# draftAccelTemp.net
KiCad netlist of a schematic drawn in EAGLE
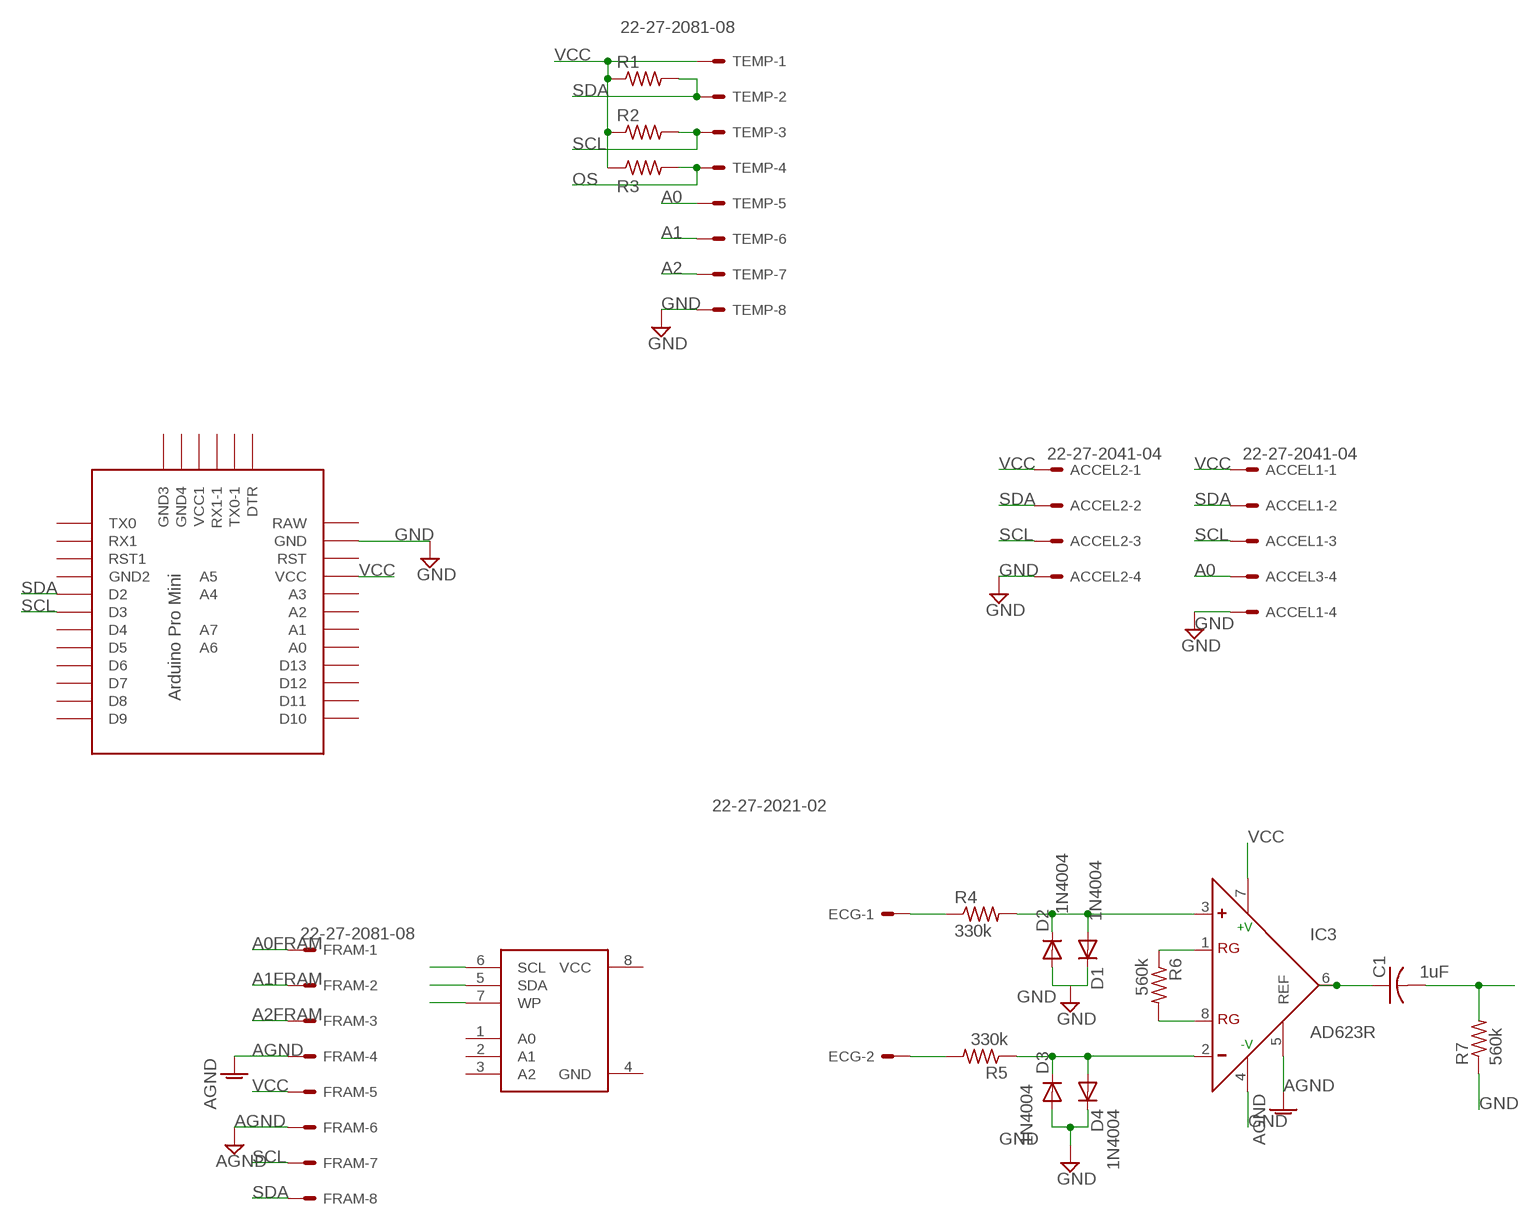
[diagram p0: schematic, sheet 1]

(export (version "E")
  (design (tool "Eeschema 10.0.6"))
  (components
    (comp (ref "ACCEL1")
      (value "22-27-2041-04")
      (footprint "eagle-import:6410-04")
      (fields (field (name "MF") "MOLEX"))
      (libsource (lib "eagle-import") (part "22-?-0427-2041"))
    )
    (comp (ref "ACCEL2")
      (value "22-27-2041-04")
      (footprint "eagle-import:6410-04")
      (fields (field (name "MF") "MOLEX"))
      (libsource (lib "eagle-import") (part "22-?-0427-2041"))
    )
    (comp (ref "ACCEL3")
      (value "22-27-2041-04")
      (footprint "eagle-import:6410-04")
      (fields (field (name "MF") "MOLEX"))
      (libsource (lib "eagle-import") (part "22-?-0427-2041"))
    )
    (comp (ref "C1")
      (value "1uF")
      (footprint "eagle-import:C0805")
      (libsource (lib "eagle-import") (part "C-USC0805"))
    )
    (comp (ref "D1")
      (value "1N4004")
      (footprint "eagle-import:DO41-10")
      (libsource (lib "eagle-import") (part "1N4004"))
    )
    (comp (ref "D2")
      (value "1N4004")
      (footprint "eagle-import:DO41-10")
      (libsource (lib "eagle-import") (part "1N4004"))
    )
    (comp (ref "D3")
      (value "1N4004")
      (footprint "eagle-import:DO41-10")
      (libsource (lib "eagle-import") (part "1N4004"))
    )
    (comp (ref "D4")
      (value "1N4004")
      (footprint "eagle-import:DO41-10")
      (libsource (lib "eagle-import") (part "1N4004"))
    )
    (comp (ref "ECG")
      (value "22-27-2021-02")
      (footprint "eagle-import:6410-02")
      (fields (field (name "MF") "MOLEX"))
      (libsource (lib "eagle-import") (part "22-?-0227-2021"))
    )
    (comp (ref "FRAM")
      (value "22-27-2081-08")
      (footprint "eagle-import:6410-08")
      (fields (field (name "MF") "MOLEX"))
      (libsource (lib "eagle-import") (part "22-?-0827-2081"))
    )
    (comp (ref "IC3")
      (value "AD623R")
      (footprint "eagle-import:SO8")
      (fields (field (name "MPN") "AD623ARZ."))
      (libsource (lib "eagle-import") (part "AD623R"))
    )
    (comp (ref "R1")
      (value "R-US_R0805")
      (footprint "eagle-import:R0805")
      (libsource (lib "eagle-import") (part "R-US_R0805"))
    )
    (comp (ref "R2")
      (value "R-US_R0805")
      (footprint "eagle-import:R0805")
      (libsource (lib "eagle-import") (part "R-US_R0805"))
    )
    (comp (ref "R3")
      (value "R-US_R0805")
      (footprint "eagle-import:R0805")
      (libsource (lib "eagle-import") (part "R-US_R0805"))
    )
    (comp (ref "R4")
      (value "330k")
      (footprint "eagle-import:R0805")
      (libsource (lib "eagle-import") (part "R-US_R0805"))
    )
    (comp (ref "R5")
      (value "330k")
      (footprint "eagle-import:R0805")
      (libsource (lib "eagle-import") (part "R-US_R0805"))
    )
    (comp (ref "R6")
      (value "560k")
      (footprint "eagle-import:R0805")
      (libsource (lib "eagle-import") (part "R-US_R0805"))
    )
    (comp (ref "R7")
      (value "560k")
      (footprint "eagle-import:R0805")
      (libsource (lib "eagle-import") (part "R-US_R0805"))
    )
    (comp (ref "TEMP")
      (value "22-27-2081-08")
      (footprint "eagle-import:6410-08")
      (fields (field (name "MF") "MOLEX"))
      (libsource (lib "eagle-import") (part "22-?-0827-2081"))
    )
    (comp (ref "U$1")
      (value "PRO-MINI-2")
      (footprint "eagle-import:PRO-MINI-2")
      (libsource (lib "eagle-import") (part "PRO-MINI-2"))
    )
    (comp (ref "U2")
      (value "MB85RC256VPF-G-JNERE2")
      (footprint "eagle-import:SOIC8")
      (libsource (lib "eagle-import") (part "MB85RC256VPF-G-JNERE2"))
    )
  )
  (nets
    (net (code "1") (name "/A0") (class "Default")
      (node (ref "ACCEL3") (pin "4") (pinfunction "S_4") (pintype "passive"))
      (node (ref "TEMP") (pin "5") (pinfunction "S_5") (pintype "passive"))
    )
    (net (code "2") (name "/A0FRAM") (class "Default")
      (node (ref "FRAM") (pin "1") (pinfunction "S_1") (pintype "passive"))
    )
    (net (code "3") (name "/A1") (class "Default")
      (node (ref "TEMP") (pin "6") (pinfunction "S_6") (pintype "passive"))
    )
    (net (code "4") (name "/A1FRAM") (class "Default")
      (node (ref "FRAM") (pin "2") (pinfunction "S_2") (pintype "passive"))
    )
    (net (code "5") (name "/A2") (class "Default")
      (node (ref "TEMP") (pin "7") (pinfunction "S_7") (pintype "passive"))
    )
    (net (code "6") (name "/A2FRAM") (class "Default")
      (node (ref "FRAM") (pin "3") (pinfunction "S_3") (pintype "passive"))
    )
    (net (code "7") (name "/OS") (class "Default")
      (node (ref "R3") (pin "2") (pinfunction "2_2") (pintype "passive"))
      (node (ref "TEMP") (pin "4") (pinfunction "S_4") (pintype "passive"))
    )
    (net (code "8") (name "/SCL") (class "Default")
      (node (ref "ACCEL1") (pin "3") (pinfunction "S_3") (pintype "passive"))
      (node (ref "ACCEL2") (pin "3") (pinfunction "S_3") (pintype "passive"))
      (node (ref "FRAM") (pin "7") (pinfunction "S_7") (pintype "passive"))
      (node (ref "R2") (pin "2") (pinfunction "2_2") (pintype "passive"))
      (node (ref "TEMP") (pin "3") (pinfunction "S_3") (pintype "passive"))
      (node (ref "U$1") (pin "D3") (pinfunction "D3_D3") (pintype "bidirectional"))
    )
    (net (code "9") (name "/SDA") (class "Default")
      (node (ref "ACCEL1") (pin "2") (pinfunction "S_2") (pintype "passive"))
      (node (ref "ACCEL2") (pin "2") (pinfunction "S_2") (pintype "passive"))
      (node (ref "FRAM") (pin "8") (pinfunction "S_8") (pintype "passive"))
      (node (ref "R1") (pin "2") (pinfunction "2_2") (pintype "passive"))
      (node (ref "TEMP") (pin "2") (pinfunction "S_2") (pintype "passive"))
      (node (ref "U$1") (pin "D2") (pinfunction "D2_D2") (pintype "bidirectional"))
    )
    (net (code "10") (name "/VCC") (class "Default")
      (node (ref "ACCEL1") (pin "1") (pinfunction "S_1") (pintype "passive"))
      (node (ref "ACCEL2") (pin "1") (pinfunction "S_1") (pintype "passive"))
      (node (ref "FRAM") (pin "5") (pinfunction "S_5") (pintype "passive"))
      (node (ref "IC3") (pin "7") (pinfunction "+V_7") (pintype "power_in"))
      (node (ref "R1") (pin "1") (pinfunction "1_1") (pintype "passive"))
      (node (ref "R2") (pin "1") (pinfunction "1_1") (pintype "passive"))
      (node (ref "R3") (pin "1") (pinfunction "1_1") (pintype "passive"))
      (node (ref "TEMP") (pin "1") (pinfunction "S_1") (pintype "passive"))
      (node (ref "U$1") (pin "VCC") (pinfunction "VCC_VCC") (pintype "bidirectional"))
    )
    (net (code "11") (name "AGND") (class "Default")
      (node (ref "FRAM") (pin "4") (pinfunction "S_4") (pintype "passive"))
      (node (ref "FRAM") (pin "6") (pinfunction "S_6") (pintype "passive"))
      (node (ref "IC3") (pin "5") (pinfunction "REF_5") (pintype "passive"))
    )
    (net (code "12") (name "GND") (class "Default")
      (node (ref "ACCEL1") (pin "4") (pinfunction "S_4") (pintype "passive"))
      (node (ref "ACCEL2") (pin "4") (pinfunction "S_4") (pintype "passive"))
      (node (ref "C1") (pin "2") (pinfunction "2_2") (pintype "passive"))
      (node (ref "D1") (pin "C") (pinfunction "C_C") (pintype "passive"))
      (node (ref "D2") (pin "A") (pinfunction "A_A") (pintype "passive"))
      (node (ref "D3") (pin "A") (pinfunction "A_A") (pintype "passive"))
      (node (ref "D4") (pin "C") (pinfunction "C_C") (pintype "passive"))
      (node (ref "IC3") (pin "4") (pinfunction "-V_4") (pintype "power_in"))
      (node (ref "R7") (pin "1") (pinfunction "1_1") (pintype "passive"))
      (node (ref "R7") (pin "2") (pinfunction "2_2") (pintype "passive"))
      (node (ref "TEMP") (pin "8") (pinfunction "S_8") (pintype "passive"))
      (node (ref "U$1") (pin "GND") (pinfunction "GND_GND") (pintype "bidirectional"))
    )
    (net (code "13") (name "Net-(ECGA-S)") (class "Default")
      (node (ref "ECG") (pin "1") (pinfunction "S_1") (pintype "passive"))
      (node (ref "R4") (pin "1") (pinfunction "1_1") (pintype "passive"))
    )
    (net (code "14") (name "Net-(ECGB-S)") (class "Default")
      (node (ref "ECG") (pin "2") (pinfunction "S_2") (pintype "passive"))
      (node (ref "R5") (pin "2") (pinfunction "2_2") (pintype "passive"))
    )
    (net (code "15") (name "Net-(IC3-+)") (class "Default")
      (node (ref "D1") (pin "A") (pinfunction "A_A") (pintype "passive"))
      (node (ref "D2") (pin "C") (pinfunction "C_C") (pintype "passive"))
      (node (ref "IC3") (pin "3") (pinfunction "+_3") (pintype "input"))
      (node (ref "R4") (pin "2") (pinfunction "2_2") (pintype "passive"))
    )
    (net (code "16") (name "Net-(IC3--)") (class "Default")
      (node (ref "D3") (pin "C") (pinfunction "C_C") (pintype "passive"))
      (node (ref "D4") (pin "A") (pinfunction "A_A") (pintype "passive"))
      (node (ref "IC3") (pin "2") (pinfunction "-_2") (pintype "input"))
      (node (ref "R5") (pin "1") (pinfunction "1_1") (pintype "passive"))
    )
    (net (code "17") (name "Net-(IC3-OUT)") (class "Default")
      (node (ref "C1") (pin "1") (pinfunction "1_1") (pintype "passive"))
      (node (ref "IC3") (pin "6") (pinfunction "OUT_6") (pintype "output"))
    )
    (net (code "18") (name "Net-(IC3-RG-Pad1)") (class "Default")
      (node (ref "IC3") (pin "1") (pinfunction "RG_1") (pintype "passive"))
      (node (ref "R6") (pin "1") (pinfunction "1_1") (pintype "passive"))
    )
    (net (code "19") (name "Net-(IC3-RG-Pad8)") (class "Default")
      (node (ref "IC3") (pin "8") (pinfunction "RG_8") (pintype "passive"))
      (node (ref "R6") (pin "2") (pinfunction "2_2") (pintype "passive"))
    )
    (net (code "20") (name "unconnected-(U$1-GND2-PadGND1)") (class "Default")
      (node (ref "U$1") (pin "GND1") (pinfunction "GND2_GND1") (pintype "bidirectional"))
    )
    (net (code "21") (name "unconnected-(U$1-GND3-PadGND2)") (class "Default")
      (node (ref "U$1") (pin "GND2") (pinfunction "GND3_GND2") (pintype "bidirectional"))
    )
    (net (code "22") (name "unconnected-(U$1-GND4-PadGND3)") (class "Default")
      (node (ref "U$1") (pin "GND3") (pinfunction "GND4_GND3") (pintype "bidirectional"))
    )
    (net (code "23") (name "unconnected-(U$1-PadA0)") (class "Default")
      (node (ref "U$1") (pin "A0") (pinfunction "A0_A0") (pintype "bidirectional"))
    )
    (net (code "24") (name "unconnected-(U$1-PadA1)") (class "Default")
      (node (ref "U$1") (pin "A1") (pinfunction "A1_A1") (pintype "bidirectional"))
    )
    (net (code "25") (name "unconnected-(U$1-PadA2)") (class "Default")
      (node (ref "U$1") (pin "A2") (pinfunction "A2_A2") (pintype "bidirectional"))
    )
    (net (code "26") (name "unconnected-(U$1-PadA3)") (class "Default")
      (node (ref "U$1") (pin "A3") (pinfunction "A3_A3") (pintype "bidirectional"))
    )
    (net (code "27") (name "unconnected-(U$1-PadA4)") (class "Default")
      (node (ref "U$1") (pin "A4") (pinfunction "A4_A4") (pintype "bidirectional"))
    )
    (net (code "28") (name "unconnected-(U$1-PadA5)") (class "Default")
      (node (ref "U$1") (pin "A5") (pinfunction "A5_A5") (pintype "bidirectional"))
    )
    (net (code "29") (name "unconnected-(U$1-PadA6)") (class "Default")
      (node (ref "U$1") (pin "A6") (pinfunction "A6_A6") (pintype "bidirectional"))
    )
    (net (code "30") (name "unconnected-(U$1-PadA7)") (class "Default")
      (node (ref "U$1") (pin "A7") (pinfunction "A7_A7") (pintype "bidirectional"))
    )
    (net (code "31") (name "unconnected-(U$1-PadD4)") (class "Default")
      (node (ref "U$1") (pin "D4") (pinfunction "D4_D4") (pintype "bidirectional"))
    )
    (net (code "32") (name "unconnected-(U$1-PadD5)") (class "Default")
      (node (ref "U$1") (pin "D5") (pinfunction "D5_D5") (pintype "bidirectional"))
    )
    (net (code "33") (name "unconnected-(U$1-PadD6)") (class "Default")
      (node (ref "U$1") (pin "D6") (pinfunction "D6_D6") (pintype "bidirectional"))
    )
    (net (code "34") (name "unconnected-(U$1-PadD7)") (class "Default")
      (node (ref "U$1") (pin "D7") (pinfunction "D7_D7") (pintype "bidirectional"))
    )
    (net (code "35") (name "unconnected-(U$1-PadD8)") (class "Default")
      (node (ref "U$1") (pin "D8") (pinfunction "D8_D8") (pintype "bidirectional"))
    )
    (net (code "36") (name "unconnected-(U$1-PadD9)") (class "Default")
      (node (ref "U$1") (pin "D9") (pinfunction "D9_D9") (pintype "bidirectional"))
    )
    (net (code "37") (name "unconnected-(U$1-PadD10)") (class "Default")
      (node (ref "U$1") (pin "D10") (pinfunction "D10_D10") (pintype "bidirectional"))
    )
    (net (code "38") (name "unconnected-(U$1-PadD11)") (class "Default")
      (node (ref "U$1") (pin "D11") (pinfunction "D11_D11") (pintype "bidirectional"))
    )
    (net (code "39") (name "unconnected-(U$1-PadD12)") (class "Default")
      (node (ref "U$1") (pin "D12") (pinfunction "D12_D12") (pintype "bidirectional"))
    )
    (net (code "40") (name "unconnected-(U$1-PadD13)") (class "Default")
      (node (ref "U$1") (pin "D13") (pinfunction "D13_D13") (pintype "bidirectional"))
    )
    (net (code "41") (name "unconnected-(U$1-PadDTR)") (class "Default")
      (node (ref "U$1") (pin "DTR") (pinfunction "DTR_DTR") (pintype "bidirectional"))
    )
    (net (code "42") (name "unconnected-(U$1-PadRAW)") (class "Default")
      (node (ref "U$1") (pin "RAW") (pinfunction "RAW_RAW") (pintype "bidirectional"))
    )
    (net (code "43") (name "unconnected-(U$1-PadRST)") (class "Default")
      (node (ref "U$1") (pin "RST") (pinfunction "RST_RST") (pintype "bidirectional"))
    )
    (net (code "44") (name "unconnected-(U$1-PadRST1)") (class "Default")
      (node (ref "U$1") (pin "RST1") (pinfunction "RST1_RST1") (pintype "bidirectional"))
    )
    (net (code "45") (name "unconnected-(U$1-PadRX1)") (class "Default")
      (node (ref "U$1") (pin "RX1") (pinfunction "RX1_RX1") (pintype "bidirectional"))
    )
    (net (code "46") (name "unconnected-(U$1-PadRX1-1)") (class "Default")
      (node (ref "U$1") (pin "RX1-1") (pinfunction "RX1-1_RX1-1") (pintype "bidirectional"))
    )
    (net (code "47") (name "unconnected-(U$1-PadTX0)") (class "Default")
      (node (ref "U$1") (pin "TX0") (pinfunction "TX0_TX0") (pintype "bidirectional"))
    )
    (net (code "48") (name "unconnected-(U$1-PadTX0-1)") (class "Default")
      (node (ref "U$1") (pin "TX0-1") (pinfunction "TX0-1_TX0-1") (pintype "bidirectional"))
    )
    (net (code "49") (name "unconnected-(U$1-PadVCC1)") (class "Default")
      (node (ref "U$1") (pin "VCC1") (pinfunction "VCC1_VCC1") (pintype "bidirectional"))
    )
    (net (code "50") (name "unconnected-(U2-A0-Pad1)") (class "Default")
      (node (ref "U2") (pin "1") (pinfunction "A0_1") (pintype "bidirectional"))
    )
    (net (code "51") (name "unconnected-(U2-A1-Pad2)") (class "Default")
      (node (ref "U2") (pin "2") (pinfunction "A1_2") (pintype "bidirectional"))
    )
    (net (code "52") (name "unconnected-(U2-A2-Pad3)") (class "Default")
      (node (ref "U2") (pin "3") (pinfunction "A2_3") (pintype "bidirectional"))
    )
    (net (code "53") (name "unconnected-(U2-GND-Pad4)") (class "Default")
      (node (ref "U2") (pin "4") (pinfunction "GND_4") (pintype "bidirectional"))
    )
    (net (code "54") (name "unconnected-(U2-SCL-Pad6)") (class "Default")
      (node (ref "U2") (pin "6") (pinfunction "SCL_6") (pintype "bidirectional"))
    )
    (net (code "55") (name "unconnected-(U2-SDA-Pad5)") (class "Default")
      (node (ref "U2") (pin "5") (pinfunction "SDA_5") (pintype "bidirectional"))
    )
    (net (code "56") (name "unconnected-(U2-VCC-Pad8)") (class "Default")
      (node (ref "U2") (pin "8") (pinfunction "VCC_8") (pintype "bidirectional"))
    )
    (net (code "57") (name "unconnected-(U2-WP-Pad7)") (class "Default")
      (node (ref "U2") (pin "7") (pinfunction "WP_7") (pintype "bidirectional"))
    )
  )
)
